# MCU.net
KiCad netlist of a schematic drawn in Altium Designer
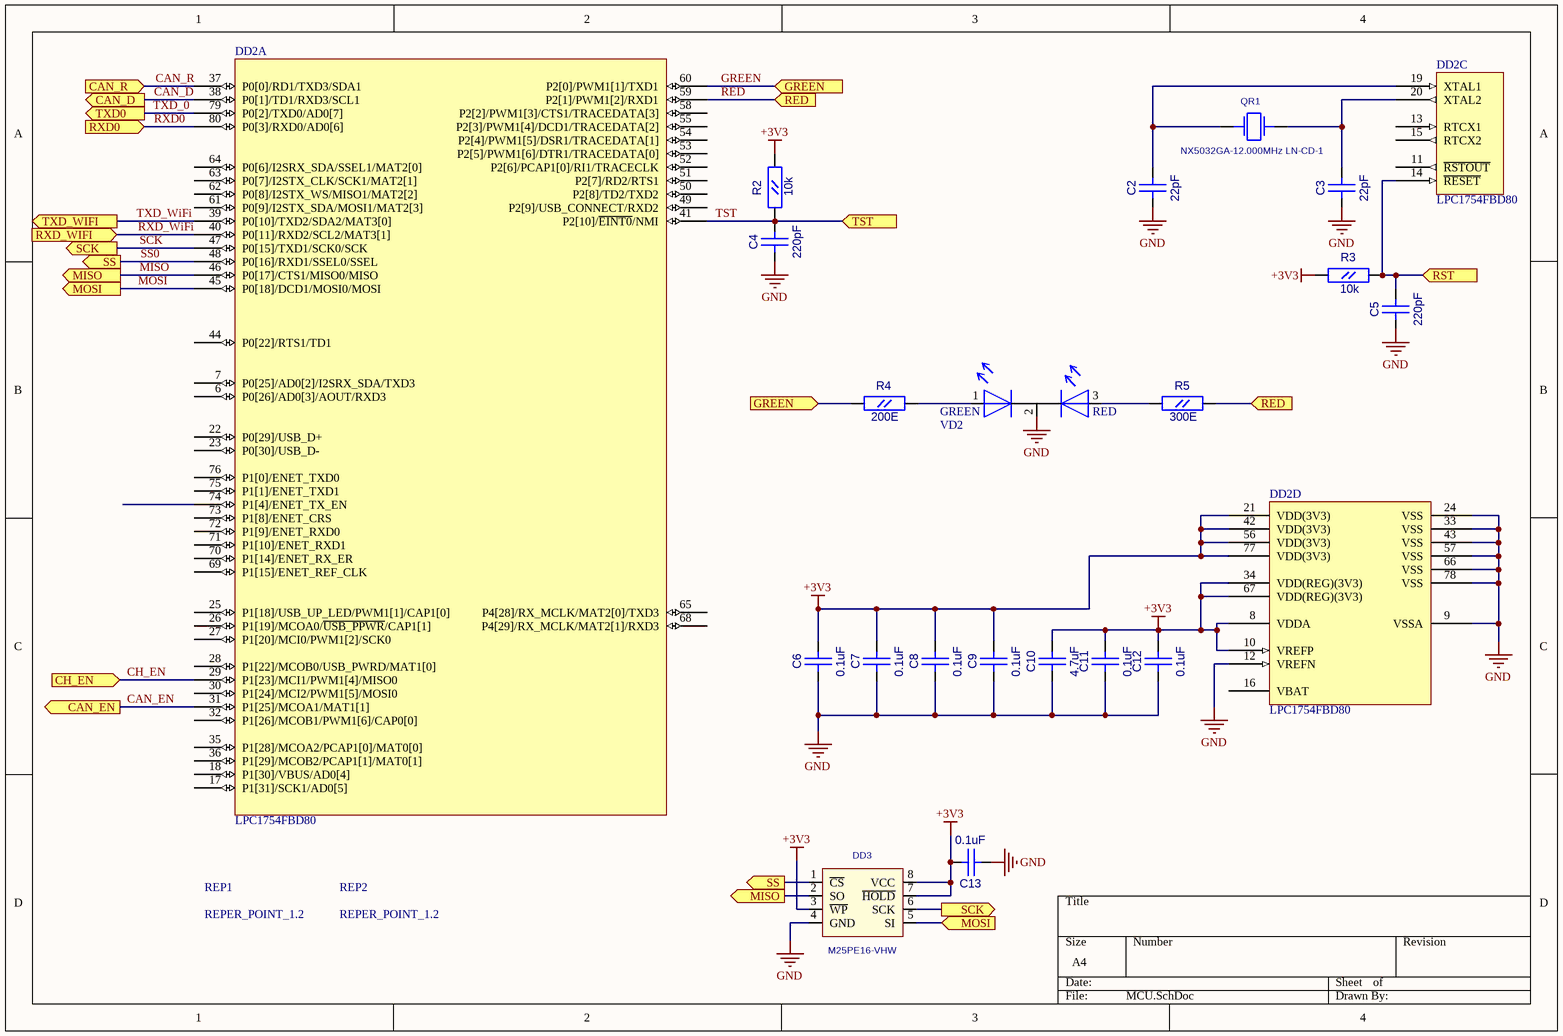
[diagram p0: MCU.SchDoc]

(export (version "E")
  (design (tool "Eeschema 10.0.6"))
  (components
    (comp (ref "C2")
      (value "22pF")
      (footprint "CC0603")
      (description "CC0603")
      (libsource (lib "gprs_modem_2") (part "CC0603"))
    )
    (comp (ref "C3")
      (value "22pF")
      (footprint "CC0603")
      (description "CC0603")
      (libsource (lib "gprs_modem_2") (part "CC0603"))
    )
    (comp (ref "C4")
      (value "220pF")
      (footprint "CC0603")
      (description "CC0603")
      (libsource (lib "gprs_modem_2") (part "CC0603"))
    )
    (comp (ref "C5")
      (value "220pF")
      (footprint "CC0603")
      (description "CC0603")
      (libsource (lib "gprs_modem_2") (part "CC0603"))
    )
    (comp (ref "C6")
      (value "0.1uF")
      (footprint "CC0603")
      (description "CC0603")
      (libsource (lib "gprs_modem_2") (part "CC0603"))
    )
    (comp (ref "C7")
      (value "0.1uF")
      (footprint "CC0603")
      (description "CC0603")
      (libsource (lib "gprs_modem_2") (part "CC0603"))
    )
    (comp (ref "C8")
      (value "0.1uF")
      (footprint "CC0603")
      (description "CC0603")
      (libsource (lib "gprs_modem_2") (part "CC0603"))
    )
    (comp (ref "C9")
      (value "0.1uF")
      (footprint "CC0603")
      (description "CC0603")
      (libsource (lib "gprs_modem_2") (part "CC0603"))
    )
    (comp (ref "C10")
      (value "4.7uF")
      (footprint "CC0805")
      (description "CC0805")
      (libsource (lib "gprs_modem_2") (part "CC0805"))
    )
    (comp (ref "C11")
      (value "0.1uF")
      (footprint "CC0603")
      (description "CC0603")
      (libsource (lib "gprs_modem_2") (part "CC0603"))
    )
    (comp (ref "C12")
      (value "0.1uF")
      (footprint "CC0603")
      (description "CC0603")
      (libsource (lib "gprs_modem_2") (part "CC0603"))
    )
    (comp (ref "C13")
      (value "0.1uF")
      (footprint "CC0603")
      (description "CC0603")
      (libsource (lib "gprs_modem_2") (part "CC0603"))
    )
    (comp (ref "DD2")
      (value "LPC1754FBD80")
      (footprint "TQFP-80_0.5")
      (description "Cortex -M3 32-Bit Microcontroller, 128KB Flash, 64KB RAM, 800-Lead LQFP")
      (libsource (lib "gprs_modem_2") (part "LPC1754FBD80"))
    )
    (comp (ref "DD3")
      (value "M25PE16-VHW")
      (footprint "EIAJ_SO8")
      (description "S25FL016A0LMFI01")
      (libsource (lib "gprs_modem_2") (part "S25FL016A0LMFI01"))
    )
    (comp (ref "QR1")
      (value "NX5032GA-12.000MHz LN-CD-1")
      (footprint "AC5032_2")
      (description "AC5032/2")
      (libsource (lib "gprs_modem_2") (part "AC5032_2"))
    )
    (comp (ref "R2")
      (value "10k")
      (footprint "RC0603")
      (description "RC0603")
      (libsource (lib "gprs_modem_2") (part "RC0603"))
    )
    (comp (ref "R3")
      (value "10k")
      (footprint "RC0603")
      (description "RC0603")
      (libsource (lib "gprs_modem_2") (part "RC0603"))
    )
    (comp (ref "R4")
      (value "200E")
      (footprint "RC0603")
      (description "RC0603")
      (libsource (lib "gprs_modem_2") (part "RC0603"))
    )
    (comp (ref "R5")
      (value "300E")
      (footprint "RC0603")
      (description "RC0603")
      (libsource (lib "gprs_modem_2") (part "RC0603"))
    )
    (comp (ref "REP1")
      (value "REPER_POINT_1.2")
      (footprint "REPER1.2")
      (description "REPER1.2")
      (libsource (lib "gprs_modem_2") (part "REPER1.2"))
    )
    (comp (ref "REP2")
      (value "REPER_POINT_1.2")
      (footprint "REPER1.2")
      (description "REPER1.2")
      (libsource (lib "gprs_modem_2") (part "REPER1.2"))
    )
    (comp (ref "VD2")
      (value "GNL3015UEUGW")
      (footprint "GNL3015")
      (libsource (lib "gprs_modem_2") (part "GNL3015-UEUGW"))
    )
  )
  (nets
    (net (code "1") (name "+3V3") (class "Default")
      (node (ref "C10") (pin "2") (pinfunction "B_2") (pintype "passive"))
      (node (ref "C11") (pin "2") (pinfunction "B_2") (pintype "passive"))
      (node (ref "C12") (pin "2") (pinfunction "B_2") (pintype "passive"))
      (node (ref "C13") (pin "2") (pinfunction "B_2") (pintype "passive"))
      (node (ref "C6") (pin "2") (pinfunction "B_2") (pintype "passive"))
      (node (ref "C7") (pin "2") (pinfunction "B_2") (pintype "passive"))
      (node (ref "C8") (pin "2") (pinfunction "B_2") (pintype "passive"))
      (node (ref "C9") (pin "2") (pinfunction "B_2") (pintype "passive"))
      (node (ref "DD2") (pin "10") (pinfunction "VREFP_10") (pintype "input"))
      (node (ref "DD2") (pin "21") (pinfunction "VDD(3V3)_21") (pintype "power_in"))
      (node (ref "DD2") (pin "34") (pinfunction "VDD(REG)(3V3)_34") (pintype "power_in"))
      (node (ref "DD2") (pin "42") (pinfunction "VDD(3V3)_42") (pintype "power_in"))
      (node (ref "DD2") (pin "56") (pinfunction "VDD(3V3)_56") (pintype "power_in"))
      (node (ref "DD2") (pin "67") (pinfunction "VDD(REG)(3V3)_67") (pintype "power_in"))
      (node (ref "DD2") (pin "77") (pinfunction "VDD(3V3)_77") (pintype "power_in"))
      (node (ref "DD2") (pin "8") (pinfunction "VDDA_8") (pintype "power_in"))
      (node (ref "DD3") (pin "3") (pinfunction "~{WP}_3") (pintype "passive"))
      (node (ref "DD3") (pin "7") (pinfunction "~{HOLD}_7") (pintype "passive"))
      (node (ref "DD3") (pin "8") (pinfunction "VCC_8") (pintype "passive"))
      (node (ref "R2") (pin "2") (pinfunction "B_2") (pintype "passive"))
      (node (ref "R3") (pin "1") (pinfunction "A_1") (pintype "passive"))
    )
    (net (code "2") (name "/CAN_D") (class "Default")
      (node (ref "DD2") (pin "38") (pinfunction "P0[1]/TD1/RXD3/SCL1_38") (pintype "bidirectional"))
    )
    (net (code "3") (name "/CAN_EN") (class "Default")
      (node (ref "DD2") (pin "31") (pinfunction "P1[25]/MCOA1/MAT1[1]_31") (pintype "bidirectional"))
    )
    (net (code "4") (name "/CAN_R") (class "Default")
      (node (ref "DD2") (pin "37") (pinfunction "P0[0]/RD1/TXD3/SDA1_37") (pintype "bidirectional"))
    )
    (net (code "5") (name "/CH_EN") (class "Default")
      (node (ref "DD2") (pin "29") (pinfunction "P1[23]/MCI1/PWM1[4]/MISO0_29") (pintype "bidirectional"))
    )
    (net (code "6") (name "/GREEN") (class "Default")
      (node (ref "DD2") (pin "60") (pinfunction "P2[0]/PWM1[1]/TXD1_60") (pintype "bidirectional"))
      (node (ref "R4") (pin "1") (pinfunction "A_1") (pintype "passive"))
    )
    (net (code "7") (name "/MISO") (class "Default")
      (node (ref "DD2") (pin "46") (pinfunction "P0[17]/CTS1/MISO0/MISO_46") (pintype "bidirectional"))
      (node (ref "DD3") (pin "2") (pinfunction "SO_2") (pintype "passive"))
    )
    (net (code "8") (name "/MOSI") (class "Default")
      (node (ref "DD2") (pin "45") (pinfunction "P0[18]/DCD1/MOSI0/MOSI_45") (pintype "bidirectional"))
      (node (ref "DD3") (pin "5") (pinfunction "SI_5") (pintype "passive"))
    )
    (net (code "9") (name "/RED") (class "Default")
      (node (ref "DD2") (pin "59") (pinfunction "P2[1]/PWM1[2]/RXD1_59") (pintype "bidirectional"))
      (node (ref "R5") (pin "2") (pinfunction "B_2") (pintype "passive"))
    )
    (net (code "10") (name "/RST") (class "Default")
      (node (ref "C5") (pin "2") (pinfunction "B_2") (pintype "passive"))
      (node (ref "DD2") (pin "14") (pinfunction "~{RESET}_14") (pintype "input"))
      (node (ref "R3") (pin "2") (pinfunction "B_2") (pintype "passive"))
    )
    (net (code "11") (name "/RXD0") (class "Default")
      (node (ref "DD2") (pin "80") (pinfunction "P0[3]/RXD0/AD0[6]_80") (pintype "bidirectional"))
    )
    (net (code "12") (name "/RXD_WiFi") (class "Default")
      (node (ref "DD2") (pin "40") (pinfunction "P0[11]/RXD2/SCL2/MAT3[1]_40") (pintype "bidirectional"))
    )
    (net (code "13") (name "/SCK") (class "Default")
      (node (ref "DD2") (pin "47") (pinfunction "P0[15]/TXD1/SCK0/SCK_47") (pintype "bidirectional"))
      (node (ref "DD3") (pin "6") (pinfunction "SCK_6") (pintype "passive"))
    )
    (net (code "14") (name "/SS0") (class "Default")
      (node (ref "DD2") (pin "48") (pinfunction "P0[16]/RXD1/SSEL0/SSEL_48") (pintype "bidirectional"))
      (node (ref "DD3") (pin "1") (pinfunction "~{CS}_1") (pintype "passive"))
    )
    (net (code "15") (name "/TST") (class "Default")
      (node (ref "C4") (pin "2") (pinfunction "B_2") (pintype "passive"))
      (node (ref "DD2") (pin "41") (pinfunction "P2[10]/~{EINT0}/NMI_41") (pintype "bidirectional"))
      (node (ref "R2") (pin "1") (pinfunction "A_1") (pintype "passive"))
    )
    (net (code "16") (name "/TXD_0") (class "Default")
      (node (ref "DD2") (pin "79") (pinfunction "P0[2]/TXD0/AD0[7]_79") (pintype "bidirectional"))
    )
    (net (code "17") (name "/TXD_WiFi") (class "Default")
      (node (ref "DD2") (pin "39") (pinfunction "P0[10]/TXD2/SDA2/MAT3[0]_39") (pintype "bidirectional"))
    )
    (net (code "18") (name "GND") (class "Default")
      (node (ref "C10") (pin "1") (pinfunction "A_1") (pintype "passive"))
      (node (ref "C11") (pin "1") (pinfunction "A_1") (pintype "passive"))
      (node (ref "C12") (pin "1") (pinfunction "A_1") (pintype "passive"))
      (node (ref "C13") (pin "1") (pinfunction "A_1") (pintype "passive"))
      (node (ref "C2") (pin "1") (pinfunction "A_1") (pintype "passive"))
      (node (ref "C3") (pin "1") (pinfunction "A_1") (pintype "passive"))
      (node (ref "C4") (pin "1") (pinfunction "A_1") (pintype "passive"))
      (node (ref "C5") (pin "1") (pinfunction "A_1") (pintype "passive"))
      (node (ref "C6") (pin "1") (pinfunction "A_1") (pintype "passive"))
      (node (ref "C7") (pin "1") (pinfunction "A_1") (pintype "passive"))
      (node (ref "C8") (pin "1") (pinfunction "A_1") (pintype "passive"))
      (node (ref "C9") (pin "1") (pinfunction "A_1") (pintype "passive"))
      (node (ref "DD2") (pin "12") (pinfunction "VREFN_12") (pintype "input"))
      (node (ref "DD2") (pin "24") (pinfunction "VSS_24") (pintype "power_in"))
      (node (ref "DD2") (pin "33") (pinfunction "VSS_33") (pintype "power_in"))
      (node (ref "DD2") (pin "43") (pinfunction "VSS_43") (pintype "power_in"))
      (node (ref "DD2") (pin "57") (pinfunction "VSS_57") (pintype "power_in"))
      (node (ref "DD2") (pin "66") (pinfunction "VSS_66") (pintype "power_in"))
      (node (ref "DD2") (pin "78") (pinfunction "VSS_78") (pintype "power_in"))
      (node (ref "DD2") (pin "9") (pinfunction "VSSA_9") (pintype "power_in"))
      (node (ref "DD3") (pin "4") (pinfunction "GND_4") (pintype "passive"))
      (node (ref "VD2") (pin "2") (pinfunction "3_2") (pintype "passive"))
    )
    (net (code "19") (name "Net-(C2-B)") (class "Default")
      (node (ref "C2") (pin "2") (pinfunction "B_2") (pintype "passive"))
      (node (ref "DD2") (pin "19") (pinfunction "XTAL1_19") (pintype "input"))
      (node (ref "QR1") (pin "1") (pintype "passive"))
    )
    (net (code "20") (name "Net-(C3-B)") (class "Default")
      (node (ref "C3") (pin "2") (pinfunction "B_2") (pintype "passive"))
      (node (ref "DD2") (pin "20") (pinfunction "XTAL2_20") (pintype "output"))
      (node (ref "QR1") (pin "2") (pintype "passive"))
    )
    (net (code "21") (name "Net-(R4-B)") (class "Default")
      (node (ref "R4") (pin "2") (pinfunction "B_2") (pintype "passive"))
      (node (ref "VD2") (pin "1") (pinfunction "G_1") (pintype "passive"))
    )
    (net (code "22") (name "Net-(R5-A)") (class "Default")
      (node (ref "R5") (pin "1") (pinfunction "A_1") (pintype "passive"))
      (node (ref "VD2") (pin "3") (pintype "passive"))
    )
    (net (code "23") (name "unconnected-(DD2A-P0[6]{slash}I2SRX_SDA{slash}SSEL1{slash}MAT2[0]-Pad64)") (class "Default")
      (node (ref "DD2") (pin "64") (pinfunction "P0[6]/I2SRX_SDA/SSEL1/MAT2[0]_64") (pintype "bidirectional"))
    )
    (net (code "24") (name "unconnected-(DD2A-P0[7]{slash}I2STX_CLK{slash}SCK1{slash}MAT2[1]-Pad63)") (class "Default")
      (node (ref "DD2") (pin "63") (pinfunction "P0[7]/I2STX_CLK/SCK1/MAT2[1]_63") (pintype "bidirectional"))
    )
    (net (code "25") (name "unconnected-(DD2A-P0[8]{slash}I2STX_WS{slash}MISO1{slash}MAT2[2]-Pad62)") (class "Default")
      (node (ref "DD2") (pin "62") (pinfunction "P0[8]/I2STX_WS/MISO1/MAT2[2]_62") (pintype "bidirectional"))
    )
    (net (code "26") (name "unconnected-(DD2A-P0[9]{slash}I2STX_SDA{slash}MOSI1{slash}MAT2[3]-Pad61)") (class "Default")
      (node (ref "DD2") (pin "61") (pinfunction "P0[9]/I2STX_SDA/MOSI1/MAT2[3]_61") (pintype "bidirectional"))
    )
    (net (code "27") (name "unconnected-(DD2A-P0[22]{slash}RTS1{slash}TD1-Pad44)") (class "Default")
      (node (ref "DD2") (pin "44") (pinfunction "P0[22]/RTS1/TD1_44") (pintype "bidirectional"))
    )
    (net (code "28") (name "unconnected-(DD2A-P0[25]{slash}AD0[2]{slash}I2SRX_SDA{slash}TXD3-Pad7)") (class "Default")
      (node (ref "DD2") (pin "7") (pinfunction "P0[25]/AD0[2]/I2SRX_SDA/TXD3_7") (pintype "bidirectional"))
    )
    (net (code "29") (name "unconnected-(DD2A-P0[26]{slash}AD0[3]{slash}AOUT{slash}RXD3-Pad6)") (class "Default")
      (node (ref "DD2") (pin "6") (pinfunction "P0[26]/AD0[3]/AOUT/RXD3_6") (pintype "bidirectional"))
    )
    (net (code "30") (name "unconnected-(DD2A-P0[29]{slash}USB_D+-Pad22)") (class "Default")
      (node (ref "DD2") (pin "22") (pinfunction "P0[29]/USB_D+_22") (pintype "bidirectional"))
    )
    (net (code "31") (name "unconnected-(DD2A-P0[30]{slash}USB_D--Pad23)") (class "Default")
      (node (ref "DD2") (pin "23") (pinfunction "P0[30]/USB_D-_23") (pintype "bidirectional"))
    )
    (net (code "32") (name "unconnected-(DD2A-P1[0]{slash}ENET_TXD0-Pad76)") (class "Default")
      (node (ref "DD2") (pin "76") (pinfunction "P1[0]/ENET_TXD0_76") (pintype "bidirectional"))
    )
    (net (code "33") (name "unconnected-(DD2A-P1[1]{slash}ENET_TXD1-Pad75)") (class "Default")
      (node (ref "DD2") (pin "75") (pinfunction "P1[1]/ENET_TXD1_75") (pintype "bidirectional"))
    )
    (net (code "34") (name "unconnected-(DD2A-P1[4]{slash}ENET_TX_EN-Pad74)") (class "Default")
      (node (ref "DD2") (pin "74") (pinfunction "P1[4]/ENET_TX_EN_74") (pintype "bidirectional"))
    )
    (net (code "35") (name "unconnected-(DD2A-P1[8]{slash}ENET_CRS-Pad73)") (class "Default")
      (node (ref "DD2") (pin "73") (pinfunction "P1[8]/ENET_CRS_73") (pintype "bidirectional"))
    )
    (net (code "36") (name "unconnected-(DD2A-P1[9]{slash}ENET_RXD0-Pad72)") (class "Default")
      (node (ref "DD2") (pin "72") (pinfunction "P1[9]/ENET_RXD0_72") (pintype "bidirectional"))
    )
    (net (code "37") (name "unconnected-(DD2A-P1[10]{slash}ENET_RXD1-Pad71)") (class "Default")
      (node (ref "DD2") (pin "71") (pinfunction "P1[10]/ENET_RXD1_71") (pintype "bidirectional"))
    )
    (net (code "38") (name "unconnected-(DD2A-P1[14]{slash}ENET_RX_ER-Pad70)") (class "Default")
      (node (ref "DD2") (pin "70") (pinfunction "P1[14]/ENET_RX_ER_70") (pintype "bidirectional"))
    )
    (net (code "39") (name "unconnected-(DD2A-P1[15]{slash}ENET_REF_CLK-Pad69)") (class "Default")
      (node (ref "DD2") (pin "69") (pinfunction "P1[15]/ENET_REF_CLK_69") (pintype "bidirectional"))
    )
    (net (code "40") (name "unconnected-(DD2A-P1[18]{slash}USB_UP_LED{slash}PWM1[1]{slash}CAP1[0]-Pad25)") (class "Default")
      (node (ref "DD2") (pin "25") (pinfunction "P1[18]/USB_UP_LED/PWM1[1]/CAP1[0]_25") (pintype "bidirectional"))
    )
    (net (code "41") (name "unconnected-(DD2A-P1[19]{slash}MCOA0{slash}~{USB_PPWR}{slash}CAP1[1]-Pad26)") (class "Default")
      (node (ref "DD2") (pin "26") (pinfunction "P1[19]/MCOA0/~{USB_PPWR}/CAP1[1]_26") (pintype "bidirectional"))
    )
    (net (code "42") (name "unconnected-(DD2A-P1[20]{slash}MCI0{slash}PWM1[2]{slash}SCK0-Pad27)") (class "Default")
      (node (ref "DD2") (pin "27") (pinfunction "P1[20]/MCI0/PWM1[2]/SCK0_27") (pintype "bidirectional"))
    )
    (net (code "43") (name "unconnected-(DD2A-P1[22]{slash}MCOB0{slash}USB_PWRD{slash}MAT1[0]-Pad28)") (class "Default")
      (node (ref "DD2") (pin "28") (pinfunction "P1[22]/MCOB0/USB_PWRD/MAT1[0]_28") (pintype "bidirectional"))
    )
    (net (code "44") (name "unconnected-(DD2A-P1[24]{slash}MCI2{slash}PWM1[5]{slash}MOSI0-Pad30)") (class "Default")
      (node (ref "DD2") (pin "30") (pinfunction "P1[24]/MCI2/PWM1[5]/MOSI0_30") (pintype "bidirectional"))
    )
    (net (code "45") (name "unconnected-(DD2A-P1[26]{slash}MCOB1{slash}PWM1[6]{slash}CAP0[0]-Pad32)") (class "Default")
      (node (ref "DD2") (pin "32") (pinfunction "P1[26]/MCOB1/PWM1[6]/CAP0[0]_32") (pintype "bidirectional"))
    )
    (net (code "46") (name "unconnected-(DD2A-P1[28]{slash}MCOA2{slash}PCAP1[0]{slash}MAT0[0]-Pad35)") (class "Default")
      (node (ref "DD2") (pin "35") (pinfunction "P1[28]/MCOA2/PCAP1[0]/MAT0[0]_35") (pintype "bidirectional"))
    )
    (net (code "47") (name "unconnected-(DD2A-P1[29]{slash}MCOB2{slash}PCAP1[1]{slash}MAT0[1]-Pad36)") (class "Default")
      (node (ref "DD2") (pin "36") (pinfunction "P1[29]/MCOB2/PCAP1[1]/MAT0[1]_36") (pintype "bidirectional"))
    )
    (net (code "48") (name "unconnected-(DD2A-P1[30]{slash}VBUS{slash}AD0[4]-Pad18)") (class "Default")
      (node (ref "DD2") (pin "18") (pinfunction "P1[30]/VBUS/AD0[4]_18") (pintype "bidirectional"))
    )
    (net (code "49") (name "unconnected-(DD2A-P1[31]{slash}SCK1{slash}AD0[5]-Pad17)") (class "Default")
      (node (ref "DD2") (pin "17") (pinfunction "P1[31]/SCK1/AD0[5]_17") (pintype "bidirectional"))
    )
    (net (code "50") (name "unconnected-(DD2A-P2[2]{slash}PWM1[3]{slash}CTS1{slash}TRACEDATA[3]-Pad58)") (class "Default")
      (node (ref "DD2") (pin "58") (pinfunction "P2[2]/PWM1[3]/CTS1/TRACEDATA[3]_58") (pintype "bidirectional"))
    )
    (net (code "51") (name "unconnected-(DD2A-P2[3]{slash}PWM1[4]{slash}DCD1{slash}TRACEDATA[2]-Pad55)") (class "Default")
      (node (ref "DD2") (pin "55") (pinfunction "P2[3]/PWM1[4]/DCD1/TRACEDATA[2]_55") (pintype "bidirectional"))
    )
    (net (code "52") (name "unconnected-(DD2A-P2[4]{slash}PWM1[5]{slash}DSR1{slash}TRACEDATA[1]-Pad54)") (class "Default")
      (node (ref "DD2") (pin "54") (pinfunction "P2[4]/PWM1[5]/DSR1/TRACEDATA[1]_54") (pintype "bidirectional"))
    )
    (net (code "53") (name "unconnected-(DD2A-P2[5]{slash}PWM1[6]{slash}DTR1{slash}TRACEDATA[0]-Pad53)") (class "Default")
      (node (ref "DD2") (pin "53") (pinfunction "P2[5]/PWM1[6]/DTR1/TRACEDATA[0]_53") (pintype "bidirectional"))
    )
    (net (code "54") (name "unconnected-(DD2A-P2[6]{slash}PCAP1[0]{slash}RI1{slash}TRACECLK-Pad52)") (class "Default")
      (node (ref "DD2") (pin "52") (pinfunction "P2[6]/PCAP1[0]/RI1/TRACECLK_52") (pintype "bidirectional"))
    )
    (net (code "55") (name "unconnected-(DD2A-P2[7]{slash}RD2{slash}RTS1-Pad51)") (class "Default")
      (node (ref "DD2") (pin "51") (pinfunction "P2[7]/RD2/RTS1_51") (pintype "bidirectional"))
    )
    (net (code "56") (name "unconnected-(DD2A-P2[8]{slash}TD2{slash}TXD2-Pad50)") (class "Default")
      (node (ref "DD2") (pin "50") (pinfunction "P2[8]/TD2/TXD2_50") (pintype "bidirectional"))
    )
    (net (code "57") (name "unconnected-(DD2A-P2[9]{slash}USB_CONNECT{slash}RXD2-Pad49)") (class "Default")
      (node (ref "DD2") (pin "49") (pinfunction "P2[9]/USB_CONNECT/RXD2_49") (pintype "bidirectional"))
    )
    (net (code "58") (name "unconnected-(DD2A-P4[28]{slash}RX_MCLK{slash}MAT2[0]{slash}TXD3-Pad65)") (class "Default")
      (node (ref "DD2") (pin "65") (pinfunction "P4[28]/RX_MCLK/MAT2[0]/TXD3_65") (pintype "bidirectional"))
    )
    (net (code "59") (name "unconnected-(DD2A-P4[29]{slash}RX_MCLK{slash}MAT2[1]{slash}RXD3-Pad68)") (class "Default")
      (node (ref "DD2") (pin "68") (pinfunction "P4[29]/RX_MCLK/MAT2[1]/RXD3_68") (pintype "bidirectional"))
    )
    (net (code "60") (name "unconnected-(DD2C-RTCX1-Pad13)") (class "Default")
      (node (ref "DD2") (pin "13") (pinfunction "RTCX1_13") (pintype "input"))
    )
    (net (code "61") (name "unconnected-(DD2C-RTCX2-Pad15)") (class "Default")
      (node (ref "DD2") (pin "15") (pinfunction "RTCX2_15") (pintype "output"))
    )
    (net (code "62") (name "unconnected-(DD2C-~{RSTOUT}-Pad11)") (class "Default")
      (node (ref "DD2") (pin "11") (pinfunction "~{RSTOUT}_11") (pintype "output"))
    )
    (net (code "63") (name "unconnected-(DD2D-VBAT-Pad16)") (class "Default")
      (node (ref "DD2") (pin "16") (pinfunction "VBAT_16") (pintype "power_in"))
    )
    (net (code "64") (name "unconnected-(REP1-Pad1)") (class "Default")
      (node (ref "REP1") (pin "1") (pintype "passive"))
    )
    (net (code "65") (name "unconnected-(REP2-Pad1)") (class "Default")
      (node (ref "REP2") (pin "1") (pintype "passive"))
    )
  )
)
